# Carrier.net
KiCad netlist of a schematic drawn in Altium Designer
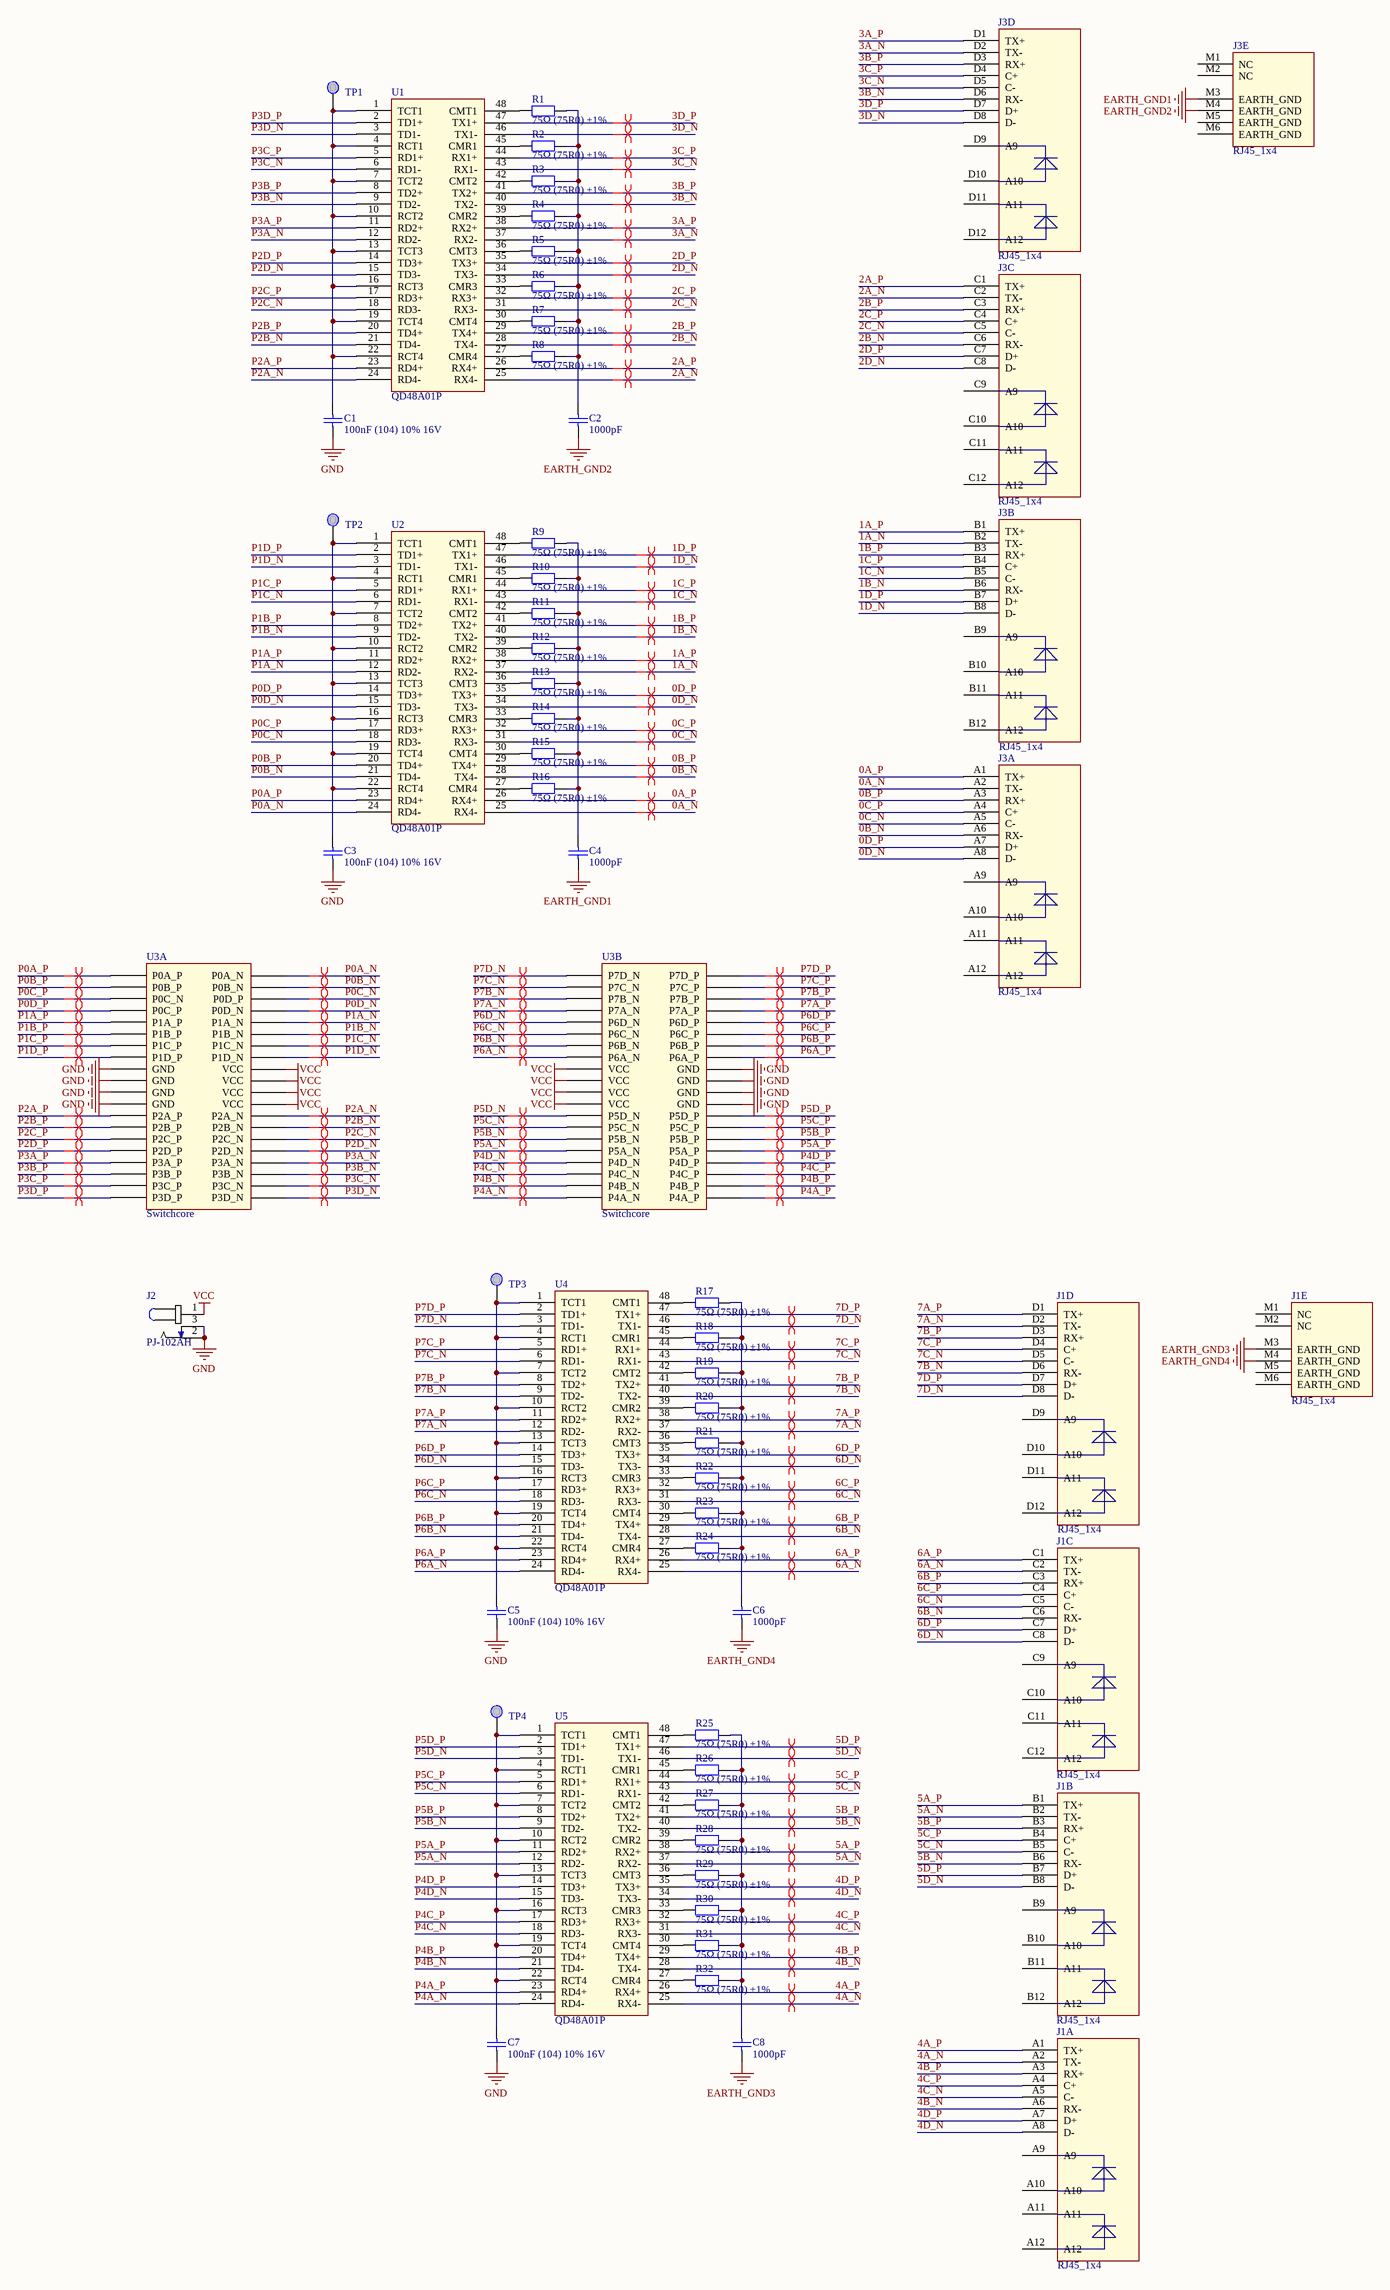
[diagram p0: Carrier.SchDoc]

(export (version "E")
  (design (tool "Eeschema 10.0.6"))
  (components
    (comp (ref "C1")
      (value "100nF (104) 10% 16V")
      (footprint "0402_C")
      (description "贴片电容")
      (libsource (lib "Miscellaneous Devices LC") (part "0402 100nF (104) 10% 16V"))
    )
    (comp (ref "C2")
      (value "1000pF")
      (footprint "CAP1210N")
      (description "CAP 1000pF ±10% 2000V (2kV) Ceramic Capacitor X7R 1210 (3225 Metric)")
      (fields
        (field (name "MANUFACTURER") "Samsung Electro-Mechanics")
        (field (name "MANUFACTURER PART NUMBER") "CL32B102KJFNNNE")
      )
      (libsource (lib "RoboteX") (part "Cap Non-Polar"))
    )
    (comp (ref "C3")
      (value "100nF (104) 10% 16V")
      (footprint "0402_C")
      (description "贴片电容")
      (libsource (lib "Miscellaneous Devices LC") (part "0402 100nF (104) 10% 16V"))
    )
    (comp (ref "C4")
      (value "1000pF")
      (footprint "CAP1210N")
      (description "CAP 1000pF ±10% 2000V (2kV) Ceramic Capacitor X7R 1210 (3225 Metric)")
      (fields
        (field (name "MANUFACTURER") "Samsung Electro-Mechanics")
        (field (name "MANUFACTURER PART NUMBER") "CL32B102KJFNNNE")
      )
      (libsource (lib "RoboteX") (part "Cap Non-Polar"))
    )
    (comp (ref "C5")
      (value "100nF (104) 10% 16V")
      (footprint "0402_C")
      (description "贴片电容")
      (libsource (lib "Miscellaneous Devices LC") (part "0402 100nF (104) 10% 16V"))
    )
    (comp (ref "C6")
      (value "1000pF")
      (footprint "CAP1210N")
      (description "CAP 1000pF ±10% 2000V (2kV) Ceramic Capacitor X7R 1210 (3225 Metric)")
      (fields
        (field (name "MANUFACTURER") "Samsung Electro-Mechanics")
        (field (name "MANUFACTURER PART NUMBER") "CL32B102KJFNNNE")
      )
      (libsource (lib "RoboteX") (part "Cap Non-Polar"))
    )
    (comp (ref "C7")
      (value "100nF (104) 10% 16V")
      (footprint "0402_C")
      (description "贴片电容")
      (libsource (lib "Miscellaneous Devices LC") (part "0402 100nF (104) 10% 16V"))
    )
    (comp (ref "C8")
      (value "1000pF")
      (footprint "CAP1210N")
      (description "CAP 1000pF ±10% 2000V (2kV) Ceramic Capacitor X7R 1210 (3225 Metric)")
      (fields
        (field (name "MANUFACTURER") "Samsung Electro-Mechanics")
        (field (name "MANUFACTURER PART NUMBER") "CL32B102KJFNNNE")
      )
      (libsource (lib "RoboteX") (part "Cap Non-Polar"))
    )
    (comp (ref "J1")
      (value "RJ45_1x4")
      (footprint "RJ45-2-5406552-0")
      (libsource (lib "Lib") (part "RJ45_1x4"))
    )
    (comp (ref "J2")
      (value "PJ-102AH")
      (footprint "CUI_PJ-102AH")
      (description "2.0 mm Center Pin, 5.0 A, Right Angle, Through Hole, Tapered Pins, Dc Power Jack Connector")
      (fields (field (name "MF") "CUI Inc.") (field (name "DIGI-KEY_PART_NUMBER") "CP-102AH-ND"))
      (libsource (lib "Lib") (part "PJ-102AH"))
    )
    (comp (ref "J3")
      (value "RJ45_1x4")
      (footprint "RJ45-2-5406552-0")
      (libsource (lib "Lib") (part "RJ45_1x4"))
    )
    (comp (ref "R1")
      (value "75Ω (75R0) ±1%")
      (footprint "0402_R")
      (description "贴片电阻")
      (libsource (lib "Miscellaneous Devices LC") (part "0402 75Ω (75R0) 1%"))
    )
    (comp (ref "R2")
      (value "75Ω (75R0) ±1%")
      (footprint "0402_R")
      (description "贴片电阻")
      (libsource (lib "Miscellaneous Devices LC") (part "0402 75Ω (75R0) 1%"))
    )
    (comp (ref "R3")
      (value "75Ω (75R0) ±1%")
      (footprint "0402_R")
      (description "贴片电阻")
      (libsource (lib "Miscellaneous Devices LC") (part "0402 75Ω (75R0) 1%"))
    )
    (comp (ref "R4")
      (value "75Ω (75R0) ±1%")
      (footprint "0402_R")
      (description "贴片电阻")
      (libsource (lib "Miscellaneous Devices LC") (part "0402 75Ω (75R0) 1%"))
    )
    (comp (ref "R5")
      (value "75Ω (75R0) ±1%")
      (footprint "0402_R")
      (description "贴片电阻")
      (libsource (lib "Miscellaneous Devices LC") (part "0402 75Ω (75R0) 1%"))
    )
    (comp (ref "R6")
      (value "75Ω (75R0) ±1%")
      (footprint "0402_R")
      (description "贴片电阻")
      (libsource (lib "Miscellaneous Devices LC") (part "0402 75Ω (75R0) 1%"))
    )
    (comp (ref "R7")
      (value "75Ω (75R0) ±1%")
      (footprint "0402_R")
      (description "贴片电阻")
      (libsource (lib "Miscellaneous Devices LC") (part "0402 75Ω (75R0) 1%"))
    )
    (comp (ref "R8")
      (value "75Ω (75R0) ±1%")
      (footprint "0402_R")
      (description "贴片电阻")
      (libsource (lib "Miscellaneous Devices LC") (part "0402 75Ω (75R0) 1%"))
    )
    (comp (ref "R9")
      (value "75Ω (75R0) ±1%")
      (footprint "0402_R")
      (description "贴片电阻")
      (libsource (lib "Miscellaneous Devices LC") (part "0402 75Ω (75R0) 1%"))
    )
    (comp (ref "R10")
      (value "75Ω (75R0) ±1%")
      (footprint "0402_R")
      (description "贴片电阻")
      (libsource (lib "Miscellaneous Devices LC") (part "0402 75Ω (75R0) 1%"))
    )
    (comp (ref "R11")
      (value "75Ω (75R0) ±1%")
      (footprint "0402_R")
      (description "贴片电阻")
      (libsource (lib "Miscellaneous Devices LC") (part "0402 75Ω (75R0) 1%"))
    )
    (comp (ref "R12")
      (value "75Ω (75R0) ±1%")
      (footprint "0402_R")
      (description "贴片电阻")
      (libsource (lib "Miscellaneous Devices LC") (part "0402 75Ω (75R0) 1%"))
    )
    (comp (ref "R13")
      (value "75Ω (75R0) ±1%")
      (footprint "0402_R")
      (description "贴片电阻")
      (libsource (lib "Miscellaneous Devices LC") (part "0402 75Ω (75R0) 1%"))
    )
    (comp (ref "R14")
      (value "75Ω (75R0) ±1%")
      (footprint "0402_R")
      (description "贴片电阻")
      (libsource (lib "Miscellaneous Devices LC") (part "0402 75Ω (75R0) 1%"))
    )
    (comp (ref "R15")
      (value "75Ω (75R0) ±1%")
      (footprint "0402_R")
      (description "贴片电阻")
      (libsource (lib "Miscellaneous Devices LC") (part "0402 75Ω (75R0) 1%"))
    )
    (comp (ref "R16")
      (value "75Ω (75R0) ±1%")
      (footprint "0402_R")
      (description "贴片电阻")
      (libsource (lib "Miscellaneous Devices LC") (part "0402 75Ω (75R0) 1%"))
    )
    (comp (ref "R17")
      (value "75Ω (75R0) ±1%")
      (footprint "0402_R")
      (description "贴片电阻")
      (libsource (lib "Miscellaneous Devices LC") (part "0402 75Ω (75R0) 1%"))
    )
    (comp (ref "R18")
      (value "75Ω (75R0) ±1%")
      (footprint "0402_R")
      (description "贴片电阻")
      (libsource (lib "Miscellaneous Devices LC") (part "0402 75Ω (75R0) 1%"))
    )
    (comp (ref "R19")
      (value "75Ω (75R0) ±1%")
      (footprint "0402_R")
      (description "贴片电阻")
      (libsource (lib "Miscellaneous Devices LC") (part "0402 75Ω (75R0) 1%"))
    )
    (comp (ref "R20")
      (value "75Ω (75R0) ±1%")
      (footprint "0402_R")
      (description "贴片电阻")
      (libsource (lib "Miscellaneous Devices LC") (part "0402 75Ω (75R0) 1%"))
    )
    (comp (ref "R21")
      (value "75Ω (75R0) ±1%")
      (footprint "0402_R")
      (description "贴片电阻")
      (libsource (lib "Miscellaneous Devices LC") (part "0402 75Ω (75R0) 1%"))
    )
    (comp (ref "R22")
      (value "75Ω (75R0) ±1%")
      (footprint "0402_R")
      (description "贴片电阻")
      (libsource (lib "Miscellaneous Devices LC") (part "0402 75Ω (75R0) 1%"))
    )
    (comp (ref "R23")
      (value "75Ω (75R0) ±1%")
      (footprint "0402_R")
      (description "贴片电阻")
      (libsource (lib "Miscellaneous Devices LC") (part "0402 75Ω (75R0) 1%"))
    )
    (comp (ref "R24")
      (value "75Ω (75R0) ±1%")
      (footprint "0402_R")
      (description "贴片电阻")
      (libsource (lib "Miscellaneous Devices LC") (part "0402 75Ω (75R0) 1%"))
    )
    (comp (ref "R25")
      (value "75Ω (75R0) ±1%")
      (footprint "0402_R")
      (description "贴片电阻")
      (libsource (lib "Miscellaneous Devices LC") (part "0402 75Ω (75R0) 1%"))
    )
    (comp (ref "R26")
      (value "75Ω (75R0) ±1%")
      (footprint "0402_R")
      (description "贴片电阻")
      (libsource (lib "Miscellaneous Devices LC") (part "0402 75Ω (75R0) 1%"))
    )
    (comp (ref "R27")
      (value "75Ω (75R0) ±1%")
      (footprint "0402_R")
      (description "贴片电阻")
      (libsource (lib "Miscellaneous Devices LC") (part "0402 75Ω (75R0) 1%"))
    )
    (comp (ref "R28")
      (value "75Ω (75R0) ±1%")
      (footprint "0402_R")
      (description "贴片电阻")
      (libsource (lib "Miscellaneous Devices LC") (part "0402 75Ω (75R0) 1%"))
    )
    (comp (ref "R29")
      (value "75Ω (75R0) ±1%")
      (footprint "0402_R")
      (description "贴片电阻")
      (libsource (lib "Miscellaneous Devices LC") (part "0402 75Ω (75R0) 1%"))
    )
    (comp (ref "R30")
      (value "75Ω (75R0) ±1%")
      (footprint "0402_R")
      (description "贴片电阻")
      (libsource (lib "Miscellaneous Devices LC") (part "0402 75Ω (75R0) 1%"))
    )
    (comp (ref "R31")
      (value "75Ω (75R0) ±1%")
      (footprint "0402_R")
      (description "贴片电阻")
      (libsource (lib "Miscellaneous Devices LC") (part "0402 75Ω (75R0) 1%"))
    )
    (comp (ref "R32")
      (value "75Ω (75R0) ±1%")
      (footprint "0402_R")
      (description "贴片电阻")
      (libsource (lib "Miscellaneous Devices LC") (part "0402 75Ω (75R0) 1%"))
    )
    (comp (ref "TP1")
      (value "Test Point, 30mil")
      (footprint "test_point_30_mil")
      (libsource (lib "RoboteX") (part "test_point"))
    )
    (comp (ref "TP2")
      (value "Test Point, 30mil")
      (footprint "test_point_30_mil")
      (libsource (lib "RoboteX") (part "test_point"))
    )
    (comp (ref "TP3")
      (value "Test Point, 30mil")
      (footprint "test_point_30_mil")
      (libsource (lib "RoboteX") (part "test_point"))
    )
    (comp (ref "TP4")
      (value "Test Point, 30mil")
      (footprint "test_point_30_mil")
      (libsource (lib "RoboteX") (part "test_point"))
    )
    (comp (ref "U1") (value "QD48A01P") (footprint "QD48A01P") (libsource (lib "Lib") (part "QD48A01P")))
    (comp (ref "U2") (value "QD48A01P") (footprint "QD48A01P") (libsource (lib "Lib") (part "QD48A01P")))
    (comp (ref "U3")
      (value "Switchcore")
      (footprint "SwitchCore")
      (libsource (lib "Lib") (part "Switchcore"))
    )
    (comp (ref "U4") (value "QD48A01P") (footprint "QD48A01P") (libsource (lib "Lib") (part "QD48A01P")))
    (comp (ref "U5") (value "QD48A01P") (footprint "QD48A01P") (libsource (lib "Lib") (part "QD48A01P")))
  )
  (nets
    (net (code "1") (name "/0A_N") (class "Default")
      (node (ref "J3") (pin "A2") (pinfunction "TX-_A2") (pintype "passive"))
      (node (ref "U2") (pin "25") (pinfunction "RX4-_25") (pintype "passive"))
    )
    (net (code "2") (name "/0A_P") (class "Default")
      (node (ref "J3") (pin "A1") (pinfunction "TX+_A1") (pintype "passive"))
      (node (ref "U2") (pin "26") (pinfunction "RX4+_26") (pintype "passive"))
    )
    (net (code "3") (name "/0B_N") (class "Default")
      (node (ref "J3") (pin "A6") (pinfunction "RX-_A6") (pintype "passive"))
      (node (ref "U2") (pin "28") (pinfunction "TX4-_28") (pintype "passive"))
    )
    (net (code "4") (name "/0B_P") (class "Default")
      (node (ref "J3") (pin "A3") (pinfunction "RX+_A3") (pintype "passive"))
      (node (ref "U2") (pin "29") (pinfunction "TX4+_29") (pintype "passive"))
    )
    (net (code "5") (name "/0C_N") (class "Default")
      (node (ref "J3") (pin "A5") (pinfunction "C-_A5") (pintype "passive"))
      (node (ref "U2") (pin "31") (pinfunction "RX3-_31") (pintype "passive"))
    )
    (net (code "6") (name "/0C_P") (class "Default")
      (node (ref "J3") (pin "A4") (pinfunction "C+_A4") (pintype "passive"))
      (node (ref "U2") (pin "32") (pinfunction "RX3+_32") (pintype "passive"))
    )
    (net (code "7") (name "/0D_N") (class "Default")
      (node (ref "J3") (pin "A8") (pinfunction "D-_A8") (pintype "passive"))
      (node (ref "U2") (pin "34") (pinfunction "TX3-_34") (pintype "passive"))
    )
    (net (code "8") (name "/0D_P") (class "Default")
      (node (ref "J3") (pin "A7") (pinfunction "D+_A7") (pintype "passive"))
      (node (ref "U2") (pin "35") (pinfunction "TX3+_35") (pintype "passive"))
    )
    (net (code "9") (name "/1A_N") (class "Default")
      (node (ref "J3") (pin "B2") (pinfunction "TX-_B2") (pintype "passive"))
      (node (ref "U2") (pin "37") (pinfunction "RX2-_37") (pintype "passive"))
    )
    (net (code "10") (name "/1A_P") (class "Default")
      (node (ref "J3") (pin "B1") (pinfunction "TX+_B1") (pintype "passive"))
      (node (ref "U2") (pin "38") (pinfunction "RX2+_38") (pintype "passive"))
    )
    (net (code "11") (name "/1B_N") (class "Default")
      (node (ref "J3") (pin "B6") (pinfunction "RX-_B6") (pintype "passive"))
      (node (ref "U2") (pin "40") (pinfunction "TX2-_40") (pintype "passive"))
    )
    (net (code "12") (name "/1B_P") (class "Default")
      (node (ref "J3") (pin "B3") (pinfunction "RX+_B3") (pintype "passive"))
      (node (ref "U2") (pin "41") (pinfunction "TX2+_41") (pintype "passive"))
    )
    (net (code "13") (name "/1C_N") (class "Default")
      (node (ref "J3") (pin "B5") (pinfunction "C-_B5") (pintype "passive"))
      (node (ref "U2") (pin "43") (pinfunction "RX1-_43") (pintype "passive"))
    )
    (net (code "14") (name "/1C_P") (class "Default")
      (node (ref "J3") (pin "B4") (pinfunction "C+_B4") (pintype "passive"))
      (node (ref "U2") (pin "44") (pinfunction "RX1+_44") (pintype "passive"))
    )
    (net (code "15") (name "/1D_N") (class "Default")
      (node (ref "J3") (pin "B8") (pinfunction "D-_B8") (pintype "passive"))
      (node (ref "U2") (pin "46") (pinfunction "TX1-_46") (pintype "passive"))
    )
    (net (code "16") (name "/1D_P") (class "Default")
      (node (ref "J3") (pin "B7") (pinfunction "D+_B7") (pintype "passive"))
      (node (ref "U2") (pin "47") (pinfunction "TX1+_47") (pintype "passive"))
    )
    (net (code "17") (name "/2A_N") (class "Default")
      (node (ref "J3") (pin "C2") (pinfunction "TX-_C2") (pintype "passive"))
      (node (ref "U1") (pin "25") (pinfunction "RX4-_25") (pintype "passive"))
    )
    (net (code "18") (name "/2A_P") (class "Default")
      (node (ref "J3") (pin "C1") (pinfunction "TX+_C1") (pintype "passive"))
      (node (ref "U1") (pin "26") (pinfunction "RX4+_26") (pintype "passive"))
    )
    (net (code "19") (name "/2B_N") (class "Default")
      (node (ref "J3") (pin "C6") (pinfunction "RX-_C6") (pintype "passive"))
      (node (ref "U1") (pin "28") (pinfunction "TX4-_28") (pintype "passive"))
    )
    (net (code "20") (name "/2B_P") (class "Default")
      (node (ref "J3") (pin "C3") (pinfunction "RX+_C3") (pintype "passive"))
      (node (ref "U1") (pin "29") (pinfunction "TX4+_29") (pintype "passive"))
    )
    (net (code "21") (name "/2C_N") (class "Default")
      (node (ref "J3") (pin "C5") (pinfunction "C-_C5") (pintype "passive"))
      (node (ref "U1") (pin "31") (pinfunction "RX3-_31") (pintype "passive"))
    )
    (net (code "22") (name "/2C_P") (class "Default")
      (node (ref "J3") (pin "C4") (pinfunction "C+_C4") (pintype "passive"))
      (node (ref "U1") (pin "32") (pinfunction "RX3+_32") (pintype "passive"))
    )
    (net (code "23") (name "/2D_N") (class "Default")
      (node (ref "J3") (pin "C8") (pinfunction "D-_C8") (pintype "passive"))
      (node (ref "U1") (pin "34") (pinfunction "TX3-_34") (pintype "passive"))
    )
    (net (code "24") (name "/2D_P") (class "Default")
      (node (ref "J3") (pin "C7") (pinfunction "D+_C7") (pintype "passive"))
      (node (ref "U1") (pin "35") (pinfunction "TX3+_35") (pintype "passive"))
    )
    (net (code "25") (name "/3A_N") (class "Default")
      (node (ref "J3") (pin "D2") (pinfunction "TX-_D2") (pintype "passive"))
      (node (ref "U1") (pin "37") (pinfunction "RX2-_37") (pintype "passive"))
    )
    (net (code "26") (name "/3A_P") (class "Default")
      (node (ref "J3") (pin "D1") (pinfunction "TX+_D1") (pintype "passive"))
      (node (ref "U1") (pin "38") (pinfunction "RX2+_38") (pintype "passive"))
    )
    (net (code "27") (name "/3B_N") (class "Default")
      (node (ref "J3") (pin "D6") (pinfunction "RX-_D6") (pintype "passive"))
      (node (ref "U1") (pin "40") (pinfunction "TX2-_40") (pintype "passive"))
    )
    (net (code "28") (name "/3B_P") (class "Default")
      (node (ref "J3") (pin "D3") (pinfunction "RX+_D3") (pintype "passive"))
      (node (ref "U1") (pin "41") (pinfunction "TX2+_41") (pintype "passive"))
    )
    (net (code "29") (name "/3C_N") (class "Default")
      (node (ref "J3") (pin "D5") (pinfunction "C-_D5") (pintype "passive"))
      (node (ref "U1") (pin "43") (pinfunction "RX1-_43") (pintype "passive"))
    )
    (net (code "30") (name "/3C_P") (class "Default")
      (node (ref "J3") (pin "D4") (pinfunction "C+_D4") (pintype "passive"))
      (node (ref "U1") (pin "44") (pinfunction "RX1+_44") (pintype "passive"))
    )
    (net (code "31") (name "/3D_N") (class "Default")
      (node (ref "J3") (pin "D8") (pinfunction "D-_D8") (pintype "passive"))
      (node (ref "U1") (pin "46") (pinfunction "TX1-_46") (pintype "passive"))
    )
    (net (code "32") (name "/3D_P") (class "Default")
      (node (ref "J3") (pin "D7") (pinfunction "D+_D7") (pintype "passive"))
      (node (ref "U1") (pin "47") (pinfunction "TX1+_47") (pintype "passive"))
    )
    (net (code "33") (name "/4A_N") (class "Default")
      (node (ref "J1") (pin "A2") (pinfunction "TX-_A2") (pintype "passive"))
      (node (ref "U5") (pin "25") (pinfunction "RX4-_25") (pintype "passive"))
    )
    (net (code "34") (name "/4A_P") (class "Default")
      (node (ref "J1") (pin "A1") (pinfunction "TX+_A1") (pintype "passive"))
      (node (ref "U5") (pin "26") (pinfunction "RX4+_26") (pintype "passive"))
    )
    (net (code "35") (name "/4B_N") (class "Default")
      (node (ref "J1") (pin "A6") (pinfunction "RX-_A6") (pintype "passive"))
      (node (ref "U5") (pin "28") (pinfunction "TX4-_28") (pintype "passive"))
    )
    (net (code "36") (name "/4B_P") (class "Default")
      (node (ref "J1") (pin "A3") (pinfunction "RX+_A3") (pintype "passive"))
      (node (ref "U5") (pin "29") (pinfunction "TX4+_29") (pintype "passive"))
    )
    (net (code "37") (name "/4C_N") (class "Default")
      (node (ref "J1") (pin "A5") (pinfunction "C-_A5") (pintype "passive"))
      (node (ref "U5") (pin "31") (pinfunction "RX3-_31") (pintype "passive"))
    )
    (net (code "38") (name "/4C_P") (class "Default")
      (node (ref "J1") (pin "A4") (pinfunction "C+_A4") (pintype "passive"))
      (node (ref "U5") (pin "32") (pinfunction "RX3+_32") (pintype "passive"))
    )
    (net (code "39") (name "/4D_N") (class "Default")
      (node (ref "J1") (pin "A8") (pinfunction "D-_A8") (pintype "passive"))
      (node (ref "U5") (pin "34") (pinfunction "TX3-_34") (pintype "passive"))
    )
    (net (code "40") (name "/4D_P") (class "Default")
      (node (ref "J1") (pin "A7") (pinfunction "D+_A7") (pintype "passive"))
      (node (ref "U5") (pin "35") (pinfunction "TX3+_35") (pintype "passive"))
    )
    (net (code "41") (name "/5A_N") (class "Default")
      (node (ref "J1") (pin "B2") (pinfunction "TX-_B2") (pintype "passive"))
      (node (ref "U5") (pin "37") (pinfunction "RX2-_37") (pintype "passive"))
    )
    (net (code "42") (name "/5A_P") (class "Default")
      (node (ref "J1") (pin "B1") (pinfunction "TX+_B1") (pintype "passive"))
      (node (ref "U5") (pin "38") (pinfunction "RX2+_38") (pintype "passive"))
    )
    (net (code "43") (name "/5B_N") (class "Default")
      (node (ref "J1") (pin "B6") (pinfunction "RX-_B6") (pintype "passive"))
      (node (ref "U5") (pin "40") (pinfunction "TX2-_40") (pintype "passive"))
    )
    (net (code "44") (name "/5B_P") (class "Default")
      (node (ref "J1") (pin "B3") (pinfunction "RX+_B3") (pintype "passive"))
      (node (ref "U5") (pin "41") (pinfunction "TX2+_41") (pintype "passive"))
    )
    (net (code "45") (name "/5C_N") (class "Default")
      (node (ref "J1") (pin "B5") (pinfunction "C-_B5") (pintype "passive"))
      (node (ref "U5") (pin "43") (pinfunction "RX1-_43") (pintype "passive"))
    )
    (net (code "46") (name "/5C_P") (class "Default")
      (node (ref "J1") (pin "B4") (pinfunction "C+_B4") (pintype "passive"))
      (node (ref "U5") (pin "44") (pinfunction "RX1+_44") (pintype "passive"))
    )
    (net (code "47") (name "/5D_N") (class "Default")
      (node (ref "J1") (pin "B8") (pinfunction "D-_B8") (pintype "passive"))
      (node (ref "U5") (pin "46") (pinfunction "TX1-_46") (pintype "passive"))
    )
    (net (code "48") (name "/5D_P") (class "Default")
      (node (ref "J1") (pin "B7") (pinfunction "D+_B7") (pintype "passive"))
      (node (ref "U5") (pin "47") (pinfunction "TX1+_47") (pintype "passive"))
    )
    (net (code "49") (name "/6A_N") (class "Default")
      (node (ref "J1") (pin "C2") (pinfunction "TX-_C2") (pintype "passive"))
      (node (ref "U4") (pin "25") (pinfunction "RX4-_25") (pintype "passive"))
    )
    (net (code "50") (name "/6A_P") (class "Default")
      (node (ref "J1") (pin "C1") (pinfunction "TX+_C1") (pintype "passive"))
      (node (ref "U4") (pin "26") (pinfunction "RX4+_26") (pintype "passive"))
    )
    (net (code "51") (name "/6B_N") (class "Default")
      (node (ref "J1") (pin "C6") (pinfunction "RX-_C6") (pintype "passive"))
      (node (ref "U4") (pin "28") (pinfunction "TX4-_28") (pintype "passive"))
    )
    (net (code "52") (name "/6B_P") (class "Default")
      (node (ref "J1") (pin "C3") (pinfunction "RX+_C3") (pintype "passive"))
      (node (ref "U4") (pin "29") (pinfunction "TX4+_29") (pintype "passive"))
    )
    (net (code "53") (name "/6C_N") (class "Default")
      (node (ref "J1") (pin "C5") (pinfunction "C-_C5") (pintype "passive"))
      (node (ref "U4") (pin "31") (pinfunction "RX3-_31") (pintype "passive"))
    )
    (net (code "54") (name "/6C_P") (class "Default")
      (node (ref "J1") (pin "C4") (pinfunction "C+_C4") (pintype "passive"))
      (node (ref "U4") (pin "32") (pinfunction "RX3+_32") (pintype "passive"))
    )
    (net (code "55") (name "/6D_N") (class "Default")
      (node (ref "J1") (pin "C8") (pinfunction "D-_C8") (pintype "passive"))
      (node (ref "U4") (pin "34") (pinfunction "TX3-_34") (pintype "passive"))
    )
    (net (code "56") (name "/6D_P") (class "Default")
      (node (ref "J1") (pin "C7") (pinfunction "D+_C7") (pintype "passive"))
      (node (ref "U4") (pin "35") (pinfunction "TX3+_35") (pintype "passive"))
    )
    (net (code "57") (name "/7A_N") (class "Default")
      (node (ref "J1") (pin "D2") (pinfunction "TX-_D2") (pintype "passive"))
      (node (ref "U4") (pin "37") (pinfunction "RX2-_37") (pintype "passive"))
    )
    (net (code "58") (name "/7A_P") (class "Default")
      (node (ref "J1") (pin "D1") (pinfunction "TX+_D1") (pintype "passive"))
      (node (ref "U4") (pin "38") (pinfunction "RX2+_38") (pintype "passive"))
    )
    (net (code "59") (name "/7B_N") (class "Default")
      (node (ref "J1") (pin "D6") (pinfunction "RX-_D6") (pintype "passive"))
      (node (ref "U4") (pin "40") (pinfunction "TX2-_40") (pintype "passive"))
    )
    (net (code "60") (name "/7B_P") (class "Default")
      (node (ref "J1") (pin "D3") (pinfunction "RX+_D3") (pintype "passive"))
      (node (ref "U4") (pin "41") (pinfunction "TX2+_41") (pintype "passive"))
    )
    (net (code "61") (name "/7C_N") (class "Default")
      (node (ref "J1") (pin "D5") (pinfunction "C-_D5") (pintype "passive"))
      (node (ref "U4") (pin "43") (pinfunction "RX1-_43") (pintype "passive"))
    )
    (net (code "62") (name "/7C_P") (class "Default")
      (node (ref "J1") (pin "D4") (pinfunction "C+_D4") (pintype "passive"))
      (node (ref "U4") (pin "44") (pinfunction "RX1+_44") (pintype "passive"))
    )
    (net (code "63") (name "/7D_N") (class "Default")
      (node (ref "J1") (pin "D8") (pinfunction "D-_D8") (pintype "passive"))
      (node (ref "U4") (pin "46") (pinfunction "TX1-_46") (pintype "passive"))
    )
    (net (code "64") (name "/7D_P") (class "Default")
      (node (ref "J1") (pin "D7") (pinfunction "D+_D7") (pintype "passive"))
      (node (ref "U4") (pin "47") (pinfunction "TX1+_47") (pintype "passive"))
    )
    (net (code "65") (name "/P0A_N") (class "Default")
      (node (ref "U2") (pin "24") (pinfunction "RD4-_24") (pintype "passive"))
      (node (ref "U3") (pin "A2") (pinfunction "P0A_N_A2") (pintype "passive"))
    )
    (net (code "66") (name "/P0A_P") (class "Default")
      (node (ref "U2") (pin "23") (pinfunction "RD4+_23") (pintype "passive"))
      (node (ref "U3") (pin "A1") (pinfunction "P0A_P_A1") (pintype "passive"))
    )
    (net (code "67") (name "/P0B_N") (class "Default")
      (node (ref "U2") (pin "21") (pinfunction "TD4-_21") (pintype "passive"))
      (node (ref "U3") (pin "A4") (pinfunction "P0B_N_A4") (pintype "passive"))
    )
    (net (code "68") (name "/P0B_P") (class "Default")
      (node (ref "U2") (pin "20") (pinfunction "TD4+_20") (pintype "passive"))
      (node (ref "U3") (pin "A3") (pinfunction "P0B_P_A3") (pintype "passive"))
    )
    (net (code "69") (name "/P0C_N") (class "Default")
      (node (ref "U2") (pin "18") (pinfunction "RD3-_18") (pintype "passive"))
      (node (ref "U3") (pin "A6") (pinfunction "P0D_P_A6") (pintype "passive"))
    )
    (net (code "70") (name "/P0C_P") (class "Default")
      (node (ref "U2") (pin "17") (pinfunction "RD3+_17") (pintype "passive"))
      (node (ref "U3") (pin "A5") (pinfunction "P0C_N_A5") (pintype "passive"))
    )
    (net (code "71") (name "/P0D_N") (class "Default")
      (node (ref "U2") (pin "15") (pinfunction "TD3-_15") (pintype "passive"))
      (node (ref "U3") (pin "A8") (pinfunction "P0D_N_A8") (pintype "passive"))
    )
    (net (code "72") (name "/P0D_P") (class "Default")
      (node (ref "U2") (pin "14") (pinfunction "TD3+_14") (pintype "passive"))
      (node (ref "U3") (pin "A7") (pinfunction "P0C_P_A7") (pintype "passive"))
    )
    (net (code "73") (name "/P1A_N") (class "Default")
      (node (ref "U2") (pin "12") (pinfunction "RD2-_12") (pintype "passive"))
      (node (ref "U3") (pin "A10") (pinfunction "P1A_N_A10") (pintype "passive"))
    )
    (net (code "74") (name "/P1A_P") (class "Default")
      (node (ref "U2") (pin "11") (pinfunction "RD2+_11") (pintype "passive"))
      (node (ref "U3") (pin "A9") (pinfunction "P1A_P_A9") (pintype "passive"))
    )
    (net (code "75") (name "/P1B_N") (class "Default")
      (node (ref "U2") (pin "9") (pinfunction "TD2-_9") (pintype "passive"))
      (node (ref "U3") (pin "A12") (pinfunction "P1B_N_A12") (pintype "passive"))
    )
    (net (code "76") (name "/P1B_P") (class "Default")
      (node (ref "U2") (pin "8") (pinfunction "TD2+_8") (pintype "passive"))
      (node (ref "U3") (pin "A11") (pinfunction "P1B_P_A11") (pintype "passive"))
    )
    (net (code "77") (name "/P1C_N") (class "Default")
      (node (ref "U2") (pin "6") (pinfunction "RD1-_6") (pintype "passive"))
      (node (ref "U3") (pin "A14") (pinfunction "P1C_N_A14") (pintype "passive"))
    )
    (net (code "78") (name "/P1C_P") (class "Default")
      (node (ref "U2") (pin "5") (pinfunction "RD1+_5") (pintype "passive"))
      (node (ref "U3") (pin "A13") (pinfunction "P1C_P_A13") (pintype "passive"))
    )
    (net (code "79") (name "/P1D_N") (class "Default")
      (node (ref "U2") (pin "3") (pinfunction "TD1-_3") (pintype "passive"))
      (node (ref "U3") (pin "A16") (pinfunction "P1D_N_A16") (pintype "passive"))
    )
    (net (code "80") (name "/P1D_P") (class "Default")
      (node (ref "U2") (pin "2") (pinfunction "TD1+_2") (pintype "passive"))
      (node (ref "U3") (pin "A15") (pinfunction "P1D_P_A15") (pintype "passive"))
    )
    (net (code "81") (name "/P2A_N") (class "Default")
      (node (ref "U1") (pin "24") (pinfunction "RD4-_24") (pintype "passive"))
      (node (ref "U3") (pin "A26") (pinfunction "P2A_N_A26") (pintype "passive"))
    )
    (net (code "82") (name "/P2A_P") (class "Default")
      (node (ref "U1") (pin "23") (pinfunction "RD4+_23") (pintype "passive"))
      (node (ref "U3") (pin "A25") (pinfunction "P2A_P_A25") (pintype "passive"))
    )
    (net (code "83") (name "/P2B_N") (class "Default")
      (node (ref "U1") (pin "21") (pinfunction "TD4-_21") (pintype "passive"))
      (node (ref "U3") (pin "A28") (pinfunction "P2B_N_A28") (pintype "passive"))
    )
    (net (code "84") (name "/P2B_P") (class "Default")
      (node (ref "U1") (pin "20") (pinfunction "TD4+_20") (pintype "passive"))
      (node (ref "U3") (pin "A27") (pinfunction "P2B_P_A27") (pintype "passive"))
    )
    (net (code "85") (name "/P2C_N") (class "Default")
      (node (ref "U1") (pin "18") (pinfunction "RD3-_18") (pintype "passive"))
      (node (ref "U3") (pin "A30") (pinfunction "P2C_N_A30") (pintype "passive"))
    )
    (net (code "86") (name "/P2C_P") (class "Default")
      (node (ref "U1") (pin "17") (pinfunction "RD3+_17") (pintype "passive"))
      (node (ref "U3") (pin "A29") (pinfunction "P2C_P_A29") (pintype "passive"))
    )
    (net (code "87") (name "/P2D_N") (class "Default")
      (node (ref "U1") (pin "15") (pinfunction "TD3-_15") (pintype "passive"))
      (node (ref "U3") (pin "A32") (pinfunction "P2D_N_A32") (pintype "passive"))
    )
    (net (code "88") (name "/P2D_P") (class "Default")
      (node (ref "U1") (pin "14") (pinfunction "TD3+_14") (pintype "passive"))
      (node (ref "U3") (pin "A31") (pinfunction "P2D_P_A31") (pintype "passive"))
    )
    (net (code "89") (name "/P3A_N") (class "Default")
      (node (ref "U1") (pin "12") (pinfunction "RD2-_12") (pintype "passive"))
      (node (ref "U3") (pin "A34") (pinfunction "P3A_N_A34") (pintype "passive"))
    )
    (net (code "90") (name "/P3A_P") (class "Default")
      (node (ref "U1") (pin "11") (pinfunction "RD2+_11") (pintype "passive"))
      (node (ref "U3") (pin "A33") (pinfunction "P3A_P_A33") (pintype "passive"))
    )
    (net (code "91") (name "/P3B_N") (class "Default")
      (node (ref "U1") (pin "9") (pinfunction "TD2-_9") (pintype "passive"))
      (node (ref "U3") (pin "A36") (pinfunction "P3B_N_A36") (pintype "passive"))
    )
    (net (code "92") (name "/P3B_P") (class "Default")
      (node (ref "U1") (pin "8") (pinfunction "TD2+_8") (pintype "passive"))
      (node (ref "U3") (pin "A35") (pinfunction "P3B_P_A35") (pintype "passive"))
    )
    (net (code "93") (name "/P3C_N") (class "Default")
      (node (ref "U1") (pin "6") (pinfunction "RD1-_6") (pintype "passive"))
      (node (ref "U3") (pin "A38") (pinfunction "P3C_N_A38") (pintype "passive"))
    )
    (net (code "94") (name "/P3C_P") (class "Default")
      (node (ref "U1") (pin "5") (pinfunction "RD1+_5") (pintype "passive"))
      (node (ref "U3") (pin "A37") (pinfunction "P3C_P_A37") (pintype "passive"))
    )
    (net (code "95") (name "/P3D_N") (class "Default")
      (node (ref "U1") (pin "3") (pinfunction "TD1-_3") (pintype "passive"))
      (node (ref "U3") (pin "A40") (pinfunction "P3D_N_A40") (pintype "passive"))
    )
    (net (code "96") (name "/P3D_P") (class "Default")
      (node (ref "U1") (pin "2") (pinfunction "TD1+_2") (pintype "passive"))
      (node (ref "U3") (pin "A39") (pinfunction "P3D_P_A39") (pintype "passive"))
    )
    (net (code "97") (name "/P4A_N") (class "Default")
      (node (ref "U3") (pin "B2") (pinfunction "P4A_N_B2") (pintype "passive"))
      (node (ref "U5") (pin "24") (pinfunction "RD4-_24") (pintype "passive"))
    )
    (net (code "98") (name "/P4A_P") (class "Default")
      (node (ref "U3") (pin "B1") (pinfunction "P4A_P_B1") (pintype "passive"))
      (node (ref "U5") (pin "23") (pinfunction "RD4+_23") (pintype "passive"))
    )
    (net (code "99") (name "/P4B_N") (class "Default")
      (node (ref "U3") (pin "B4") (pinfunction "P4B_N_B4") (pintype "passive"))
      (node (ref "U5") (pin "21") (pinfunction "TD4-_21") (pintype "passive"))
    )
    (net (code "100") (name "/P4B_P") (class "Default")
      (node (ref "U3") (pin "B3") (pinfunction "P4B_P_B3") (pintype "passive"))
      (node (ref "U5") (pin "20") (pinfunction "TD4+_20") (pintype "passive"))
    )
    (net (code "101") (name "/P4C_N") (class "Default")
      (node (ref "U3") (pin "B6") (pinfunction "P4C_N_B6") (pintype "passive"))
      (node (ref "U5") (pin "18") (pinfunction "RD3-_18") (pintype "passive"))
    )
    (net (code "102") (name "/P4C_P") (class "Default")
      (node (ref "U3") (pin "B5") (pinfunction "P4C_P_B5") (pintype "passive"))
      (node (ref "U5") (pin "17") (pinfunction "RD3+_17") (pintype "passive"))
    )
    (net (code "103") (name "/P4D_N") (class "Default")
      (node (ref "U3") (pin "B8") (pinfunction "P4D_N_B8") (pintype "passive"))
      (node (ref "U5") (pin "15") (pinfunction "TD3-_15") (pintype "passive"))
    )
    (net (code "104") (name "/P4D_P") (class "Default")
      (node (ref "U3") (pin "B7") (pinfunction "P4D_P_B7") (pintype "passive"))
      (node (ref "U5") (pin "14") (pinfunction "TD3+_14") (pintype "passive"))
    )
    (net (code "105") (name "/P5A_N") (class "Default")
      (node (ref "U3") (pin "B10") (pinfunction "P5A_N_B10") (pintype "passive"))
      (node (ref "U5") (pin "12") (pinfunction "RD2-_12") (pintype "passive"))
    )
    (net (code "106") (name "/P5A_P") (class "Default")
      (node (ref "U3") (pin "B9") (pinfunction "P5A_P_B9") (pintype "passive"))
      (node (ref "U5") (pin "11") (pinfunction "RD2+_11") (pintype "passive"))
    )
    (net (code "107") (name "/P5B_N") (class "Default")
      (node (ref "U3") (pin "B12") (pinfunction "P5B_N_B12") (pintype "passive"))
      (node (ref "U5") (pin "9") (pinfunction "TD2-_9") (pintype "passive"))
    )
    (net (code "108") (name "/P5B_P") (class "Default")
      (node (ref "U3") (pin "B11") (pinfunction "P5B_P_B11") (pintype "passive"))
      (node (ref "U5") (pin "8") (pinfunction "TD2+_8") (pintype "passive"))
    )
    (net (code "109") (name "/P5C_N") (class "Default")
      (node (ref "U3") (pin "B14") (pinfunction "P5C_N_B14") (pintype "passive"))
      (node (ref "U5") (pin "6") (pinfunction "RD1-_6") (pintype "passive"))
    )
    (net (code "110") (name "/P5C_P") (class "Default")
      (node (ref "U3") (pin "B13") (pinfunction "P5C_P_B13") (pintype "passive"))
      (node (ref "U5") (pin "5") (pinfunction "RD1+_5") (pintype "passive"))
    )
    (net (code "111") (name "/P5D_N") (class "Default")
      (node (ref "U3") (pin "B16") (pinfunction "P5D_N_B16") (pintype "passive"))
      (node (ref "U5") (pin "3") (pinfunction "TD1-_3") (pintype "passive"))
    )
    (net (code "112") (name "/P5D_P") (class "Default")
      (node (ref "U3") (pin "B15") (pinfunction "P5D_P_B15") (pintype "passive"))
      (node (ref "U5") (pin "2") (pinfunction "TD1+_2") (pintype "passive"))
    )
    (net (code "113") (name "/P6A_N") (class "Default")
      (node (ref "U3") (pin "B26") (pinfunction "P6A_N_B26") (pintype "passive"))
      (node (ref "U4") (pin "24") (pinfunction "RD4-_24") (pintype "passive"))
    )
    (net (code "114") (name "/P6A_P") (class "Default")
      (node (ref "U3") (pin "B25") (pinfunction "P6A_P_B25") (pintype "passive"))
      (node (ref "U4") (pin "23") (pinfunction "RD4+_23") (pintype "passive"))
    )
    (net (code "115") (name "/P6B_N") (class "Default")
      (node (ref "U3") (pin "B28") (pinfunction "P6B_N_B28") (pintype "passive"))
      (node (ref "U4") (pin "21") (pinfunction "TD4-_21") (pintype "passive"))
    )
    (net (code "116") (name "/P6B_P") (class "Default")
      (node (ref "U3") (pin "B27") (pinfunction "P6B_P_B27") (pintype "passive"))
      (node (ref "U4") (pin "20") (pinfunction "TD4+_20") (pintype "passive"))
    )
    (net (code "117") (name "/P6C_N") (class "Default")
      (node (ref "U3") (pin "B30") (pinfunction "P6C_N_B30") (pintype "passive"))
      (node (ref "U4") (pin "18") (pinfunction "RD3-_18") (pintype "passive"))
    )
    (net (code "118") (name "/P6C_P") (class "Default")
      (node (ref "U3") (pin "B29") (pinfunction "P6C_P_B29") (pintype "passive"))
      (node (ref "U4") (pin "17") (pinfunction "RD3+_17") (pintype "passive"))
    )
    (net (code "119") (name "/P6D_N") (class "Default")
      (node (ref "U3") (pin "B32") (pinfunction "P6D_N_B32") (pintype "passive"))
      (node (ref "U4") (pin "15") (pinfunction "TD3-_15") (pintype "passive"))
    )
    (net (code "120") (name "/P6D_P") (class "Default")
      (node (ref "U3") (pin "B31") (pinfunction "P6D_P_B31") (pintype "passive"))
      (node (ref "U4") (pin "14") (pinfunction "TD3+_14") (pintype "passive"))
    )
    (net (code "121") (name "/P7A_N") (class "Default")
      (node (ref "U3") (pin "B34") (pinfunction "P7A_N_B34") (pintype "passive"))
      (node (ref "U4") (pin "12") (pinfunction "RD2-_12") (pintype "passive"))
    )
    (net (code "122") (name "/P7A_P") (class "Default")
      (node (ref "U3") (pin "B33") (pinfunction "P7A_P_B33") (pintype "passive"))
      (node (ref "U4") (pin "11") (pinfunction "RD2+_11") (pintype "passive"))
    )
    (net (code "123") (name "/P7B_N") (class "Default")
      (node (ref "U3") (pin "B36") (pinfunction "P7B_N_B36") (pintype "passive"))
      (node (ref "U4") (pin "9") (pinfunction "TD2-_9") (pintype "passive"))
    )
    (net (code "124") (name "/P7B_P") (class "Default")
      (node (ref "U3") (pin "B35") (pinfunction "P7B_P_B35") (pintype "passive"))
      (node (ref "U4") (pin "8") (pinfunction "TD2+_8") (pintype "passive"))
    )
    (net (code "125") (name "/P7C_N") (class "Default")
      (node (ref "U3") (pin "B38") (pinfunction "P7C_N_B38") (pintype "passive"))
      (node (ref "U4") (pin "6") (pinfunction "RD1-_6") (pintype "passive"))
    )
    (net (code "126") (name "/P7C_P") (class "Default")
      (node (ref "U3") (pin "B37") (pinfunction "P7C_P_B37") (pintype "passive"))
      (node (ref "U4") (pin "5") (pinfunction "RD1+_5") (pintype "passive"))
    )
    (net (code "127") (name "/P7D_N") (class "Default")
      (node (ref "U3") (pin "B40") (pinfunction "P7D_N_B40") (pintype "passive"))
      (node (ref "U4") (pin "3") (pinfunction "TD1-_3") (pintype "passive"))
    )
    (net (code "128") (name "/P7D_P") (class "Default")
      (node (ref "U3") (pin "B39") (pinfunction "P7D_P_B39") (pintype "passive"))
      (node (ref "U4") (pin "2") (pinfunction "TD1+_2") (pintype "passive"))
    )
    (net (code "129") (name "EARTH_GND1") (class "Default")
      (node (ref "C4") (pin "1") (pinfunction "1_1") (pintype "passive"))
      (node (ref "J3") (pin "M3") (pinfunction "EARTH_GND_M3") (pintype "passive"))
    )
    (net (code "130") (name "EARTH_GND2") (class "Default")
      (node (ref "C2") (pin "1") (pinfunction "1_1") (pintype "passive"))
      (node (ref "J3") (pin "M4") (pinfunction "EARTH_GND_M4") (pintype "passive"))
    )
    (net (code "131") (name "EARTH_GND3") (class "Default")
      (node (ref "C8") (pin "1") (pinfunction "1_1") (pintype "passive"))
      (node (ref "J1") (pin "M3") (pinfunction "EARTH_GND_M3") (pintype "passive"))
    )
    (net (code "132") (name "EARTH_GND4") (class "Default")
      (node (ref "C6") (pin "1") (pinfunction "1_1") (pintype "passive"))
      (node (ref "J1") (pin "M4") (pinfunction "EARTH_GND_M4") (pintype "passive"))
    )
    (net (code "133") (name "GND") (class "Default")
      (node (ref "C1") (pin "1") (pinfunction "1_1") (pintype "passive"))
      (node (ref "C3") (pin "1") (pinfunction "1_1") (pintype "passive"))
      (node (ref "C5") (pin "1") (pinfunction "1_1") (pintype "passive"))
      (node (ref "C7") (pin "1") (pinfunction "1_1") (pintype "passive"))
      (node (ref "J2") (pin "2") (pinfunction "2_2") (pintype "passive"))
      (node (ref "J2") (pin "3") (pinfunction "3_3") (pintype "passive"))
      (node (ref "U3") (pin "A17") (pinfunction "GND_A17") (pintype "passive"))
      (node (ref "U3") (pin "A19") (pinfunction "GND_A19") (pintype "passive"))
      (node (ref "U3") (pin "A21") (pinfunction "GND_A21") (pintype "passive"))
      (node (ref "U3") (pin "A23") (pinfunction "GND_A23") (pintype "passive"))
      (node (ref "U3") (pin "B17") (pinfunction "GND_B17") (pintype "passive"))
      (node (ref "U3") (pin "B19") (pinfunction "GND_B19") (pintype "passive"))
      (node (ref "U3") (pin "B21") (pinfunction "GND_B21") (pintype "passive"))
      (node (ref "U3") (pin "B23") (pinfunction "GND_B23") (pintype "passive"))
    )
    (net (code "134") (name "Net-(C2-Pad2)") (class "Default")
      (node (ref "C2") (pin "2") (pinfunction "2_2") (pintype "passive"))
      (node (ref "R1") (pin "2") (pinfunction "2_2") (pintype "passive"))
      (node (ref "R2") (pin "2") (pinfunction "2_2") (pintype "passive"))
      (node (ref "R3") (pin "2") (pinfunction "2_2") (pintype "passive"))
      (node (ref "R4") (pin "2") (pinfunction "2_2") (pintype "passive"))
      (node (ref "R5") (pin "2") (pinfunction "2_2") (pintype "passive"))
      (node (ref "R6") (pin "2") (pinfunction "2_2") (pintype "passive"))
      (node (ref "R7") (pin "2") (pinfunction "2_2") (pintype "passive"))
      (node (ref "R8") (pin "2") (pinfunction "2_2") (pintype "passive"))
    )
    (net (code "135") (name "Net-(C4-Pad2)") (class "Default")
      (node (ref "C4") (pin "2") (pinfunction "2_2") (pintype "passive"))
      (node (ref "R10") (pin "2") (pinfunction "2_2") (pintype "passive"))
      (node (ref "R11") (pin "2") (pinfunction "2_2") (pintype "passive"))
      (node (ref "R12") (pin "2") (pinfunction "2_2") (pintype "passive"))
      (node (ref "R13") (pin "2") (pinfunction "2_2") (pintype "passive"))
      (node (ref "R14") (pin "2") (pinfunction "2_2") (pintype "passive"))
      (node (ref "R15") (pin "2") (pinfunction "2_2") (pintype "passive"))
      (node (ref "R16") (pin "2") (pinfunction "2_2") (pintype "passive"))
      (node (ref "R9") (pin "2") (pinfunction "2_2") (pintype "passive"))
    )
    (net (code "136") (name "Net-(C6-Pad2)") (class "Default")
      (node (ref "C6") (pin "2") (pinfunction "2_2") (pintype "passive"))
      (node (ref "R17") (pin "2") (pinfunction "2_2") (pintype "passive"))
      (node (ref "R18") (pin "2") (pinfunction "2_2") (pintype "passive"))
      (node (ref "R19") (pin "2") (pinfunction "2_2") (pintype "passive"))
      (node (ref "R20") (pin "2") (pinfunction "2_2") (pintype "passive"))
      (node (ref "R21") (pin "2") (pinfunction "2_2") (pintype "passive"))
      (node (ref "R22") (pin "2") (pinfunction "2_2") (pintype "passive"))
      (node (ref "R23") (pin "2") (pinfunction "2_2") (pintype "passive"))
      (node (ref "R24") (pin "2") (pinfunction "2_2") (pintype "passive"))
    )
    (net (code "137") (name "Net-(C8-Pad2)") (class "Default")
      (node (ref "C8") (pin "2") (pinfunction "2_2") (pintype "passive"))
      (node (ref "R25") (pin "2") (pinfunction "2_2") (pintype "passive"))
      (node (ref "R26") (pin "2") (pinfunction "2_2") (pintype "passive"))
      (node (ref "R27") (pin "2") (pinfunction "2_2") (pintype "passive"))
      (node (ref "R28") (pin "2") (pinfunction "2_2") (pintype "passive"))
      (node (ref "R29") (pin "2") (pinfunction "2_2") (pintype "passive"))
      (node (ref "R30") (pin "2") (pinfunction "2_2") (pintype "passive"))
      (node (ref "R31") (pin "2") (pinfunction "2_2") (pintype "passive"))
      (node (ref "R32") (pin "2") (pinfunction "2_2") (pintype "passive"))
    )
    (net (code "138") (name "Net-(U1-CMR1)") (class "Default")
      (node (ref "R2") (pin "1") (pinfunction "1_1") (pintype "passive"))
      (node (ref "U1") (pin "45") (pinfunction "CMR1_45") (pintype "passive"))
    )
    (net (code "139") (name "Net-(U1-CMR2)") (class "Default")
      (node (ref "R4") (pin "1") (pinfunction "1_1") (pintype "passive"))
      (node (ref "U1") (pin "39") (pinfunction "CMR2_39") (pintype "passive"))
    )
    (net (code "140") (name "Net-(U1-CMR3)") (class "Default")
      (node (ref "R6") (pin "1") (pinfunction "1_1") (pintype "passive"))
      (node (ref "U1") (pin "33") (pinfunction "CMR3_33") (pintype "passive"))
    )
    (net (code "141") (name "Net-(U1-CMR4)") (class "Default")
      (node (ref "R8") (pin "1") (pinfunction "1_1") (pintype "passive"))
      (node (ref "U1") (pin "27") (pinfunction "CMR4_27") (pintype "passive"))
    )
    (net (code "142") (name "Net-(U1-CMT1)") (class "Default")
      (node (ref "R1") (pin "1") (pinfunction "1_1") (pintype "passive"))
      (node (ref "U1") (pin "48") (pinfunction "CMT1_48") (pintype "passive"))
    )
    (net (code "143") (name "Net-(U1-CMT2)") (class "Default")
      (node (ref "R3") (pin "1") (pinfunction "1_1") (pintype "passive"))
      (node (ref "U1") (pin "42") (pinfunction "CMT2_42") (pintype "passive"))
    )
    (net (code "144") (name "Net-(U1-CMT3)") (class "Default")
      (node (ref "R5") (pin "1") (pinfunction "1_1") (pintype "passive"))
      (node (ref "U1") (pin "36") (pinfunction "CMT3_36") (pintype "passive"))
    )
    (net (code "145") (name "Net-(U1-CMT4)") (class "Default")
      (node (ref "R7") (pin "1") (pinfunction "1_1") (pintype "passive"))
      (node (ref "U1") (pin "30") (pinfunction "CMT4_30") (pintype "passive"))
    )
    (net (code "146") (name "Net-(U1-RCT1)") (class "Default")
      (node (ref "C1") (pin "2") (pinfunction "2_2") (pintype "passive"))
      (node (ref "TP1") (pin "0") (pinfunction "0_0") (pintype "passive"))
      (node (ref "U1") (pin "1") (pinfunction "TCT1_1") (pintype "passive"))
      (node (ref "U1") (pin "10") (pinfunction "RCT2_10") (pintype "passive"))
      (node (ref "U1") (pin "13") (pinfunction "TCT3_13") (pintype "passive"))
      (node (ref "U1") (pin "16") (pinfunction "RCT3_16") (pintype "passive"))
      (node (ref "U1") (pin "19") (pinfunction "TCT4_19") (pintype "passive"))
      (node (ref "U1") (pin "22") (pinfunction "RCT4_22") (pintype "passive"))
      (node (ref "U1") (pin "4") (pinfunction "RCT1_4") (pintype "passive"))
      (node (ref "U1") (pin "7") (pinfunction "TCT2_7") (pintype "passive"))
    )
    (net (code "147") (name "Net-(U2-CMR1)") (class "Default")
      (node (ref "R10") (pin "1") (pinfunction "1_1") (pintype "passive"))
      (node (ref "U2") (pin "45") (pinfunction "CMR1_45") (pintype "passive"))
    )
    (net (code "148") (name "Net-(U2-CMR2)") (class "Default")
      (node (ref "R12") (pin "1") (pinfunction "1_1") (pintype "passive"))
      (node (ref "U2") (pin "39") (pinfunction "CMR2_39") (pintype "passive"))
    )
    (net (code "149") (name "Net-(U2-CMR3)") (class "Default")
      (node (ref "R14") (pin "1") (pinfunction "1_1") (pintype "passive"))
      (node (ref "U2") (pin "33") (pinfunction "CMR3_33") (pintype "passive"))
    )
    (net (code "150") (name "Net-(U2-CMR4)") (class "Default")
      (node (ref "R16") (pin "1") (pinfunction "1_1") (pintype "passive"))
      (node (ref "U2") (pin "27") (pinfunction "CMR4_27") (pintype "passive"))
    )
    (net (code "151") (name "Net-(U2-CMT1)") (class "Default")
      (node (ref "R9") (pin "1") (pinfunction "1_1") (pintype "passive"))
      (node (ref "U2") (pin "48") (pinfunction "CMT1_48") (pintype "passive"))
    )
    (net (code "152") (name "Net-(U2-CMT2)") (class "Default")
      (node (ref "R11") (pin "1") (pinfunction "1_1") (pintype "passive"))
      (node (ref "U2") (pin "42") (pinfunction "CMT2_42") (pintype "passive"))
    )
    (net (code "153") (name "Net-(U2-CMT3)") (class "Default")
      (node (ref "R13") (pin "1") (pinfunction "1_1") (pintype "passive"))
      (node (ref "U2") (pin "36") (pinfunction "CMT3_36") (pintype "passive"))
    )
    (net (code "154") (name "Net-(U2-CMT4)") (class "Default")
      (node (ref "R15") (pin "1") (pinfunction "1_1") (pintype "passive"))
      (node (ref "U2") (pin "30") (pinfunction "CMT4_30") (pintype "passive"))
    )
    (net (code "155") (name "Net-(U2-RCT1)") (class "Default")
      (node (ref "C3") (pin "2") (pinfunction "2_2") (pintype "passive"))
      (node (ref "TP2") (pin "0") (pinfunction "0_0") (pintype "passive"))
      (node (ref "U2") (pin "1") (pinfunction "TCT1_1") (pintype "passive"))
      (node (ref "U2") (pin "10") (pinfunction "RCT2_10") (pintype "passive"))
      (node (ref "U2") (pin "13") (pinfunction "TCT3_13") (pintype "passive"))
      (node (ref "U2") (pin "16") (pinfunction "RCT3_16") (pintype "passive"))
      (node (ref "U2") (pin "19") (pinfunction "TCT4_19") (pintype "passive"))
      (node (ref "U2") (pin "22") (pinfunction "RCT4_22") (pintype "passive"))
      (node (ref "U2") (pin "4") (pinfunction "RCT1_4") (pintype "passive"))
      (node (ref "U2") (pin "7") (pinfunction "TCT2_7") (pintype "passive"))
    )
    (net (code "156") (name "Net-(U4-CMR1)") (class "Default")
      (node (ref "R18") (pin "1") (pinfunction "1_1") (pintype "passive"))
      (node (ref "U4") (pin "45") (pinfunction "CMR1_45") (pintype "passive"))
    )
    (net (code "157") (name "Net-(U4-CMR2)") (class "Default")
      (node (ref "R20") (pin "1") (pinfunction "1_1") (pintype "passive"))
      (node (ref "U4") (pin "39") (pinfunction "CMR2_39") (pintype "passive"))
    )
    (net (code "158") (name "Net-(U4-CMR3)") (class "Default")
      (node (ref "R22") (pin "1") (pinfunction "1_1") (pintype "passive"))
      (node (ref "U4") (pin "33") (pinfunction "CMR3_33") (pintype "passive"))
    )
    (net (code "159") (name "Net-(U4-CMR4)") (class "Default")
      (node (ref "R24") (pin "1") (pinfunction "1_1") (pintype "passive"))
      (node (ref "U4") (pin "27") (pinfunction "CMR4_27") (pintype "passive"))
    )
    (net (code "160") (name "Net-(U4-CMT1)") (class "Default")
      (node (ref "R17") (pin "1") (pinfunction "1_1") (pintype "passive"))
      (node (ref "U4") (pin "48") (pinfunction "CMT1_48") (pintype "passive"))
    )
    (net (code "161") (name "Net-(U4-CMT2)") (class "Default")
      (node (ref "R19") (pin "1") (pinfunction "1_1") (pintype "passive"))
      (node (ref "U4") (pin "42") (pinfunction "CMT2_42") (pintype "passive"))
    )
    (net (code "162") (name "Net-(U4-CMT3)") (class "Default")
      (node (ref "R21") (pin "1") (pinfunction "1_1") (pintype "passive"))
      (node (ref "U4") (pin "36") (pinfunction "CMT3_36") (pintype "passive"))
    )
    (net (code "163") (name "Net-(U4-CMT4)") (class "Default")
      (node (ref "R23") (pin "1") (pinfunction "1_1") (pintype "passive"))
      (node (ref "U4") (pin "30") (pinfunction "CMT4_30") (pintype "passive"))
    )
    (net (code "164") (name "Net-(U4-RCT1)") (class "Default")
      (node (ref "C5") (pin "2") (pinfunction "2_2") (pintype "passive"))
      (node (ref "TP3") (pin "0") (pinfunction "0_0") (pintype "passive"))
      (node (ref "U4") (pin "1") (pinfunction "TCT1_1") (pintype "passive"))
      (node (ref "U4") (pin "10") (pinfunction "RCT2_10") (pintype "passive"))
      (node (ref "U4") (pin "13") (pinfunction "TCT3_13") (pintype "passive"))
      (node (ref "U4") (pin "16") (pinfunction "RCT3_16") (pintype "passive"))
      (node (ref "U4") (pin "19") (pinfunction "TCT4_19") (pintype "passive"))
      (node (ref "U4") (pin "22") (pinfunction "RCT4_22") (pintype "passive"))
      (node (ref "U4") (pin "4") (pinfunction "RCT1_4") (pintype "passive"))
      (node (ref "U4") (pin "7") (pinfunction "TCT2_7") (pintype "passive"))
    )
    (net (code "165") (name "Net-(U5-CMR1)") (class "Default")
      (node (ref "R26") (pin "1") (pinfunction "1_1") (pintype "passive"))
      (node (ref "U5") (pin "45") (pinfunction "CMR1_45") (pintype "passive"))
    )
    (net (code "166") (name "Net-(U5-CMR2)") (class "Default")
      (node (ref "R28") (pin "1") (pinfunction "1_1") (pintype "passive"))
      (node (ref "U5") (pin "39") (pinfunction "CMR2_39") (pintype "passive"))
    )
    (net (code "167") (name "Net-(U5-CMR3)") (class "Default")
      (node (ref "R30") (pin "1") (pinfunction "1_1") (pintype "passive"))
      (node (ref "U5") (pin "33") (pinfunction "CMR3_33") (pintype "passive"))
    )
    (net (code "168") (name "Net-(U5-CMR4)") (class "Default")
      (node (ref "R32") (pin "1") (pinfunction "1_1") (pintype "passive"))
      (node (ref "U5") (pin "27") (pinfunction "CMR4_27") (pintype "passive"))
    )
    (net (code "169") (name "Net-(U5-CMT1)") (class "Default")
      (node (ref "R25") (pin "1") (pinfunction "1_1") (pintype "passive"))
      (node (ref "U5") (pin "48") (pinfunction "CMT1_48") (pintype "passive"))
    )
    (net (code "170") (name "Net-(U5-CMT2)") (class "Default")
      (node (ref "R27") (pin "1") (pinfunction "1_1") (pintype "passive"))
      (node (ref "U5") (pin "42") (pinfunction "CMT2_42") (pintype "passive"))
    )
    (net (code "171") (name "Net-(U5-CMT3)") (class "Default")
      (node (ref "R29") (pin "1") (pinfunction "1_1") (pintype "passive"))
      (node (ref "U5") (pin "36") (pinfunction "CMT3_36") (pintype "passive"))
    )
    (net (code "172") (name "Net-(U5-CMT4)") (class "Default")
      (node (ref "R31") (pin "1") (pinfunction "1_1") (pintype "passive"))
      (node (ref "U5") (pin "30") (pinfunction "CMT4_30") (pintype "passive"))
    )
    (net (code "173") (name "Net-(U5-RCT1)") (class "Default")
      (node (ref "C7") (pin "2") (pinfunction "2_2") (pintype "passive"))
      (node (ref "TP4") (pin "0") (pinfunction "0_0") (pintype "passive"))
      (node (ref "U5") (pin "1") (pinfunction "TCT1_1") (pintype "passive"))
      (node (ref "U5") (pin "10") (pinfunction "RCT2_10") (pintype "passive"))
      (node (ref "U5") (pin "13") (pinfunction "TCT3_13") (pintype "passive"))
      (node (ref "U5") (pin "16") (pinfunction "RCT3_16") (pintype "passive"))
      (node (ref "U5") (pin "19") (pinfunction "TCT4_19") (pintype "passive"))
      (node (ref "U5") (pin "22") (pinfunction "RCT4_22") (pintype "passive"))
      (node (ref "U5") (pin "4") (pinfunction "RCT1_4") (pintype "passive"))
      (node (ref "U5") (pin "7") (pinfunction "TCT2_7") (pintype "passive"))
    )
    (net (code "174") (name "VCC") (class "Default")
      (node (ref "J2") (pin "1") (pinfunction "1_1") (pintype "passive"))
      (node (ref "U3") (pin "A18") (pinfunction "VCC_A18") (pintype "passive"))
      (node (ref "U3") (pin "A20") (pinfunction "VCC_A20") (pintype "passive"))
      (node (ref "U3") (pin "A22") (pinfunction "VCC_A22") (pintype "passive"))
      (node (ref "U3") (pin "A24") (pinfunction "VCC_A24") (pintype "passive"))
      (node (ref "U3") (pin "B18") (pinfunction "VCC_B18") (pintype "passive"))
      (node (ref "U3") (pin "B20") (pinfunction "VCC_B20") (pintype "passive"))
      (node (ref "U3") (pin "B22") (pinfunction "VCC_B22") (pintype "passive"))
      (node (ref "U3") (pin "B24") (pinfunction "VCC_B24") (pintype "passive"))
    )
    (net (code "175") (name "unconnected-(J1-PadA9)") (class "Default")
      (node (ref "J1") (pin "A9") (pinfunction "A9_A9") (pintype "passive"))
    )
    (net (code "176") (name "unconnected-(J1-PadA10)") (class "Default")
      (node (ref "J1") (pin "A10") (pinfunction "A10_A10") (pintype "passive"))
    )
    (net (code "177") (name "unconnected-(J1-PadA11)") (class "Default")
      (node (ref "J1") (pin "A11") (pinfunction "A11_A11") (pintype "passive"))
    )
    (net (code "178") (name "unconnected-(J1-PadA12)") (class "Default")
      (node (ref "J1") (pin "A12") (pinfunction "A12_A12") (pintype "passive"))
    )
    (net (code "179") (name "unconnected-(J1B-A9-PadB9)") (class "Default")
      (node (ref "J1") (pin "B9") (pinfunction "A9_B9") (pintype "passive"))
    )
    (net (code "180") (name "unconnected-(J1B-A10-PadB10)") (class "Default")
      (node (ref "J1") (pin "B10") (pinfunction "A10_B10") (pintype "passive"))
    )
    (net (code "181") (name "unconnected-(J1B-A11-PadB11)") (class "Default")
      (node (ref "J1") (pin "B11") (pinfunction "A11_B11") (pintype "passive"))
    )
    (net (code "182") (name "unconnected-(J1B-A12-PadB12)") (class "Default")
      (node (ref "J1") (pin "B12") (pinfunction "A12_B12") (pintype "passive"))
    )
    (net (code "183") (name "unconnected-(J1C-A9-PadC9)") (class "Default")
      (node (ref "J1") (pin "C9") (pinfunction "A9_C9") (pintype "passive"))
    )
    (net (code "184") (name "unconnected-(J1C-A10-PadC10)") (class "Default")
      (node (ref "J1") (pin "C10") (pinfunction "A10_C10") (pintype "passive"))
    )
    (net (code "185") (name "unconnected-(J1C-A11-PadC11)") (class "Default")
      (node (ref "J1") (pin "C11") (pinfunction "A11_C11") (pintype "passive"))
    )
    (net (code "186") (name "unconnected-(J1C-A12-PadC12)") (class "Default")
      (node (ref "J1") (pin "C12") (pinfunction "A12_C12") (pintype "passive"))
    )
    (net (code "187") (name "unconnected-(J1D-A9-PadD9)") (class "Default")
      (node (ref "J1") (pin "D9") (pinfunction "A9_D9") (pintype "passive"))
    )
    (net (code "188") (name "unconnected-(J1D-A10-PadD10)") (class "Default")
      (node (ref "J1") (pin "D10") (pinfunction "A10_D10") (pintype "passive"))
    )
    (net (code "189") (name "unconnected-(J1D-A11-PadD11)") (class "Default")
      (node (ref "J1") (pin "D11") (pinfunction "A11_D11") (pintype "passive"))
    )
    (net (code "190") (name "unconnected-(J1D-A12-PadD12)") (class "Default")
      (node (ref "J1") (pin "D12") (pinfunction "A12_D12") (pintype "passive"))
    )
    (net (code "191") (name "unconnected-(J1E-EARTH_GND-PadM5)") (class "Default")
      (node (ref "J1") (pin "M5") (pinfunction "EARTH_GND_M5") (pintype "passive"))
    )
    (net (code "192") (name "unconnected-(J1E-EARTH_GND-PadM6)") (class "Default")
      (node (ref "J1") (pin "M6") (pinfunction "EARTH_GND_M6") (pintype "passive"))
    )
    (net (code "193") (name "unconnected-(J1E-NC-PadM1)") (class "Default")
      (node (ref "J1") (pin "M1") (pinfunction "NC_M1") (pintype "passive"))
    )
    (net (code "194") (name "unconnected-(J1E-NC-PadM2)") (class "Default")
      (node (ref "J1") (pin "M2") (pinfunction "NC_M2") (pintype "passive"))
    )
    (net (code "195") (name "unconnected-(J3-PadA9)") (class "Default")
      (node (ref "J3") (pin "A9") (pinfunction "A9_A9") (pintype "passive"))
    )
    (net (code "196") (name "unconnected-(J3-PadA10)") (class "Default")
      (node (ref "J3") (pin "A10") (pinfunction "A10_A10") (pintype "passive"))
    )
    (net (code "197") (name "unconnected-(J3-PadA11)") (class "Default")
      (node (ref "J3") (pin "A11") (pinfunction "A11_A11") (pintype "passive"))
    )
    (net (code "198") (name "unconnected-(J3-PadA12)") (class "Default")
      (node (ref "J3") (pin "A12") (pinfunction "A12_A12") (pintype "passive"))
    )
    (net (code "199") (name "unconnected-(J3B-A9-PadB9)") (class "Default")
      (node (ref "J3") (pin "B9") (pinfunction "A9_B9") (pintype "passive"))
    )
    (net (code "200") (name "unconnected-(J3B-A10-PadB10)") (class "Default")
      (node (ref "J3") (pin "B10") (pinfunction "A10_B10") (pintype "passive"))
    )
    (net (code "201") (name "unconnected-(J3B-A11-PadB11)") (class "Default")
      (node (ref "J3") (pin "B11") (pinfunction "A11_B11") (pintype "passive"))
    )
    (net (code "202") (name "unconnected-(J3B-A12-PadB12)") (class "Default")
      (node (ref "J3") (pin "B12") (pinfunction "A12_B12") (pintype "passive"))
    )
    (net (code "203") (name "unconnected-(J3C-A9-PadC9)") (class "Default")
      (node (ref "J3") (pin "C9") (pinfunction "A9_C9") (pintype "passive"))
    )
    (net (code "204") (name "unconnected-(J3C-A10-PadC10)") (class "Default")
      (node (ref "J3") (pin "C10") (pinfunction "A10_C10") (pintype "passive"))
    )
    (net (code "205") (name "unconnected-(J3C-A11-PadC11)") (class "Default")
      (node (ref "J3") (pin "C11") (pinfunction "A11_C11") (pintype "passive"))
    )
    (net (code "206") (name "unconnected-(J3C-A12-PadC12)") (class "Default")
      (node (ref "J3") (pin "C12") (pinfunction "A12_C12") (pintype "passive"))
    )
    (net (code "207") (name "unconnected-(J3D-A9-PadD9)") (class "Default")
      (node (ref "J3") (pin "D9") (pinfunction "A9_D9") (pintype "passive"))
    )
    (net (code "208") (name "unconnected-(J3D-A10-PadD10)") (class "Default")
      (node (ref "J3") (pin "D10") (pinfunction "A10_D10") (pintype "passive"))
    )
    (net (code "209") (name "unconnected-(J3D-A11-PadD11)") (class "Default")
      (node (ref "J3") (pin "D11") (pinfunction "A11_D11") (pintype "passive"))
    )
    (net (code "210") (name "unconnected-(J3D-A12-PadD12)") (class "Default")
      (node (ref "J3") (pin "D12") (pinfunction "A12_D12") (pintype "passive"))
    )
    (net (code "211") (name "unconnected-(J3E-EARTH_GND-PadM5)") (class "Default")
      (node (ref "J3") (pin "M5") (pinfunction "EARTH_GND_M5") (pintype "passive"))
    )
    (net (code "212") (name "unconnected-(J3E-EARTH_GND-PadM6)") (class "Default")
      (node (ref "J3") (pin "M6") (pinfunction "EARTH_GND_M6") (pintype "passive"))
    )
    (net (code "213") (name "unconnected-(J3E-NC-PadM1)") (class "Default")
      (node (ref "J3") (pin "M1") (pinfunction "NC_M1") (pintype "passive"))
    )
    (net (code "214") (name "unconnected-(J3E-NC-PadM2)") (class "Default")
      (node (ref "J3") (pin "M2") (pinfunction "NC_M2") (pintype "passive"))
    )
  )
)
